# connector.net
KiCad netlist of a schematic drawn in Altium Designer
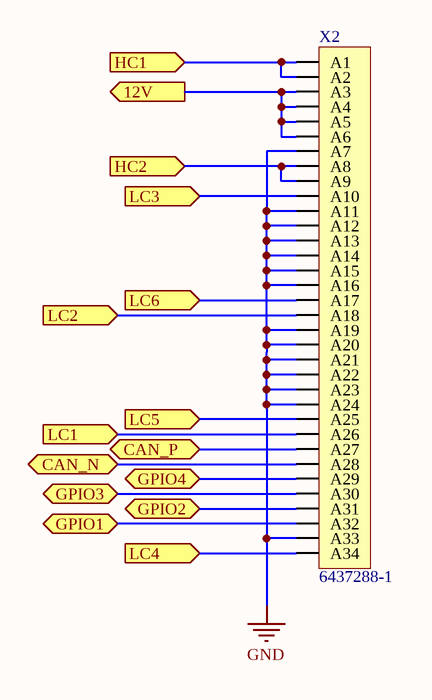
[diagram p0: connector.SchDoc]

(export (version "E")
  (design (tool "Eeschema 10.0.6"))
  (components
    (comp (ref "X2")
      (value "6437288-1")
      (footprint "6437288-1")
      (description "Superseal 34P")
      (libsource (lib "Connectors") (part "6437288-1"))
    )
  )
  (nets
    (net (code "1") (name "/12V") (class "Default")
      (node (ref "X2") (pin "A3") (pinfunction "A3_A3") (pintype "passive"))
      (node (ref "X2") (pin "A4") (pinfunction "A4_A4") (pintype "passive"))
      (node (ref "X2") (pin "A5") (pinfunction "A5_A5") (pintype "passive"))
      (node (ref "X2") (pin "A6") (pinfunction "A6_A6") (pintype "passive"))
    )
    (net (code "2") (name "/CAN_N") (class "Default")
      (node (ref "X2") (pin "A28") (pinfunction "A28_A28") (pintype "passive"))
    )
    (net (code "3") (name "/CAN_P") (class "Default")
      (node (ref "X2") (pin "A27") (pinfunction "A27_A27") (pintype "passive"))
    )
    (net (code "4") (name "/GPIO1") (class "Default")
      (node (ref "X2") (pin "A32") (pinfunction "A32_A32") (pintype "passive"))
    )
    (net (code "5") (name "/GPIO2") (class "Default")
      (node (ref "X2") (pin "A31") (pinfunction "A31_A31") (pintype "passive"))
    )
    (net (code "6") (name "/GPIO3") (class "Default")
      (node (ref "X2") (pin "A30") (pinfunction "A30_A30") (pintype "passive"))
    )
    (net (code "7") (name "/GPIO4") (class "Default")
      (node (ref "X2") (pin "A29") (pinfunction "A29_A29") (pintype "passive"))
    )
    (net (code "8") (name "/HC1") (class "Default")
      (node (ref "X2") (pin "A1") (pinfunction "A1_A1") (pintype "passive"))
      (node (ref "X2") (pin "A2") (pinfunction "A2_A2") (pintype "passive"))
    )
    (net (code "9") (name "/HC2") (class "Default")
      (node (ref "X2") (pin "A8") (pinfunction "A8_A8") (pintype "passive"))
      (node (ref "X2") (pin "A9") (pinfunction "A9_A9") (pintype "passive"))
    )
    (net (code "10") (name "/LC1") (class "Default")
      (node (ref "X2") (pin "A26") (pinfunction "A26_A26") (pintype "passive"))
    )
    (net (code "11") (name "/LC2") (class "Default")
      (node (ref "X2") (pin "A18") (pinfunction "A18_A18") (pintype "passive"))
    )
    (net (code "12") (name "/LC3") (class "Default")
      (node (ref "X2") (pin "A10") (pinfunction "A10_A10") (pintype "passive"))
    )
    (net (code "13") (name "/LC4") (class "Default")
      (node (ref "X2") (pin "A34") (pinfunction "A34_A34") (pintype "passive"))
    )
    (net (code "14") (name "/LC5") (class "Default")
      (node (ref "X2") (pin "A25") (pinfunction "A25_A25") (pintype "passive"))
    )
    (net (code "15") (name "/LC6") (class "Default")
      (node (ref "X2") (pin "A17") (pinfunction "A17_A17") (pintype "passive"))
    )
    (net (code "16") (name "GND") (class "Default")
      (node (ref "X2") (pin "A11") (pinfunction "A11_A11") (pintype "passive"))
      (node (ref "X2") (pin "A12") (pinfunction "A12_A12") (pintype "passive"))
      (node (ref "X2") (pin "A13") (pinfunction "A13_A13") (pintype "passive"))
      (node (ref "X2") (pin "A14") (pinfunction "A14_A14") (pintype "passive"))
      (node (ref "X2") (pin "A15") (pinfunction "A15_A15") (pintype "passive"))
      (node (ref "X2") (pin "A16") (pinfunction "A16_A16") (pintype "passive"))
      (node (ref "X2") (pin "A19") (pinfunction "A19_A19") (pintype "passive"))
      (node (ref "X2") (pin "A20") (pinfunction "A20_A20") (pintype "passive"))
      (node (ref "X2") (pin "A21") (pinfunction "A21_A21") (pintype "passive"))
      (node (ref "X2") (pin "A22") (pinfunction "A22_A22") (pintype "passive"))
      (node (ref "X2") (pin "A23") (pinfunction "A23_A23") (pintype "passive"))
      (node (ref "X2") (pin "A24") (pinfunction "A24_A24") (pintype "passive"))
      (node (ref "X2") (pin "A33") (pinfunction "A33_A33") (pintype "passive"))
      (node (ref "X2") (pin "A7") (pinfunction "A7_A7") (pintype "passive"))
    )
  )
)
